# 780-00036_rev1_Sch_Crate_Slot_Power_Inte.net
KiCad netlist of a schematic drawn in Altium Designer
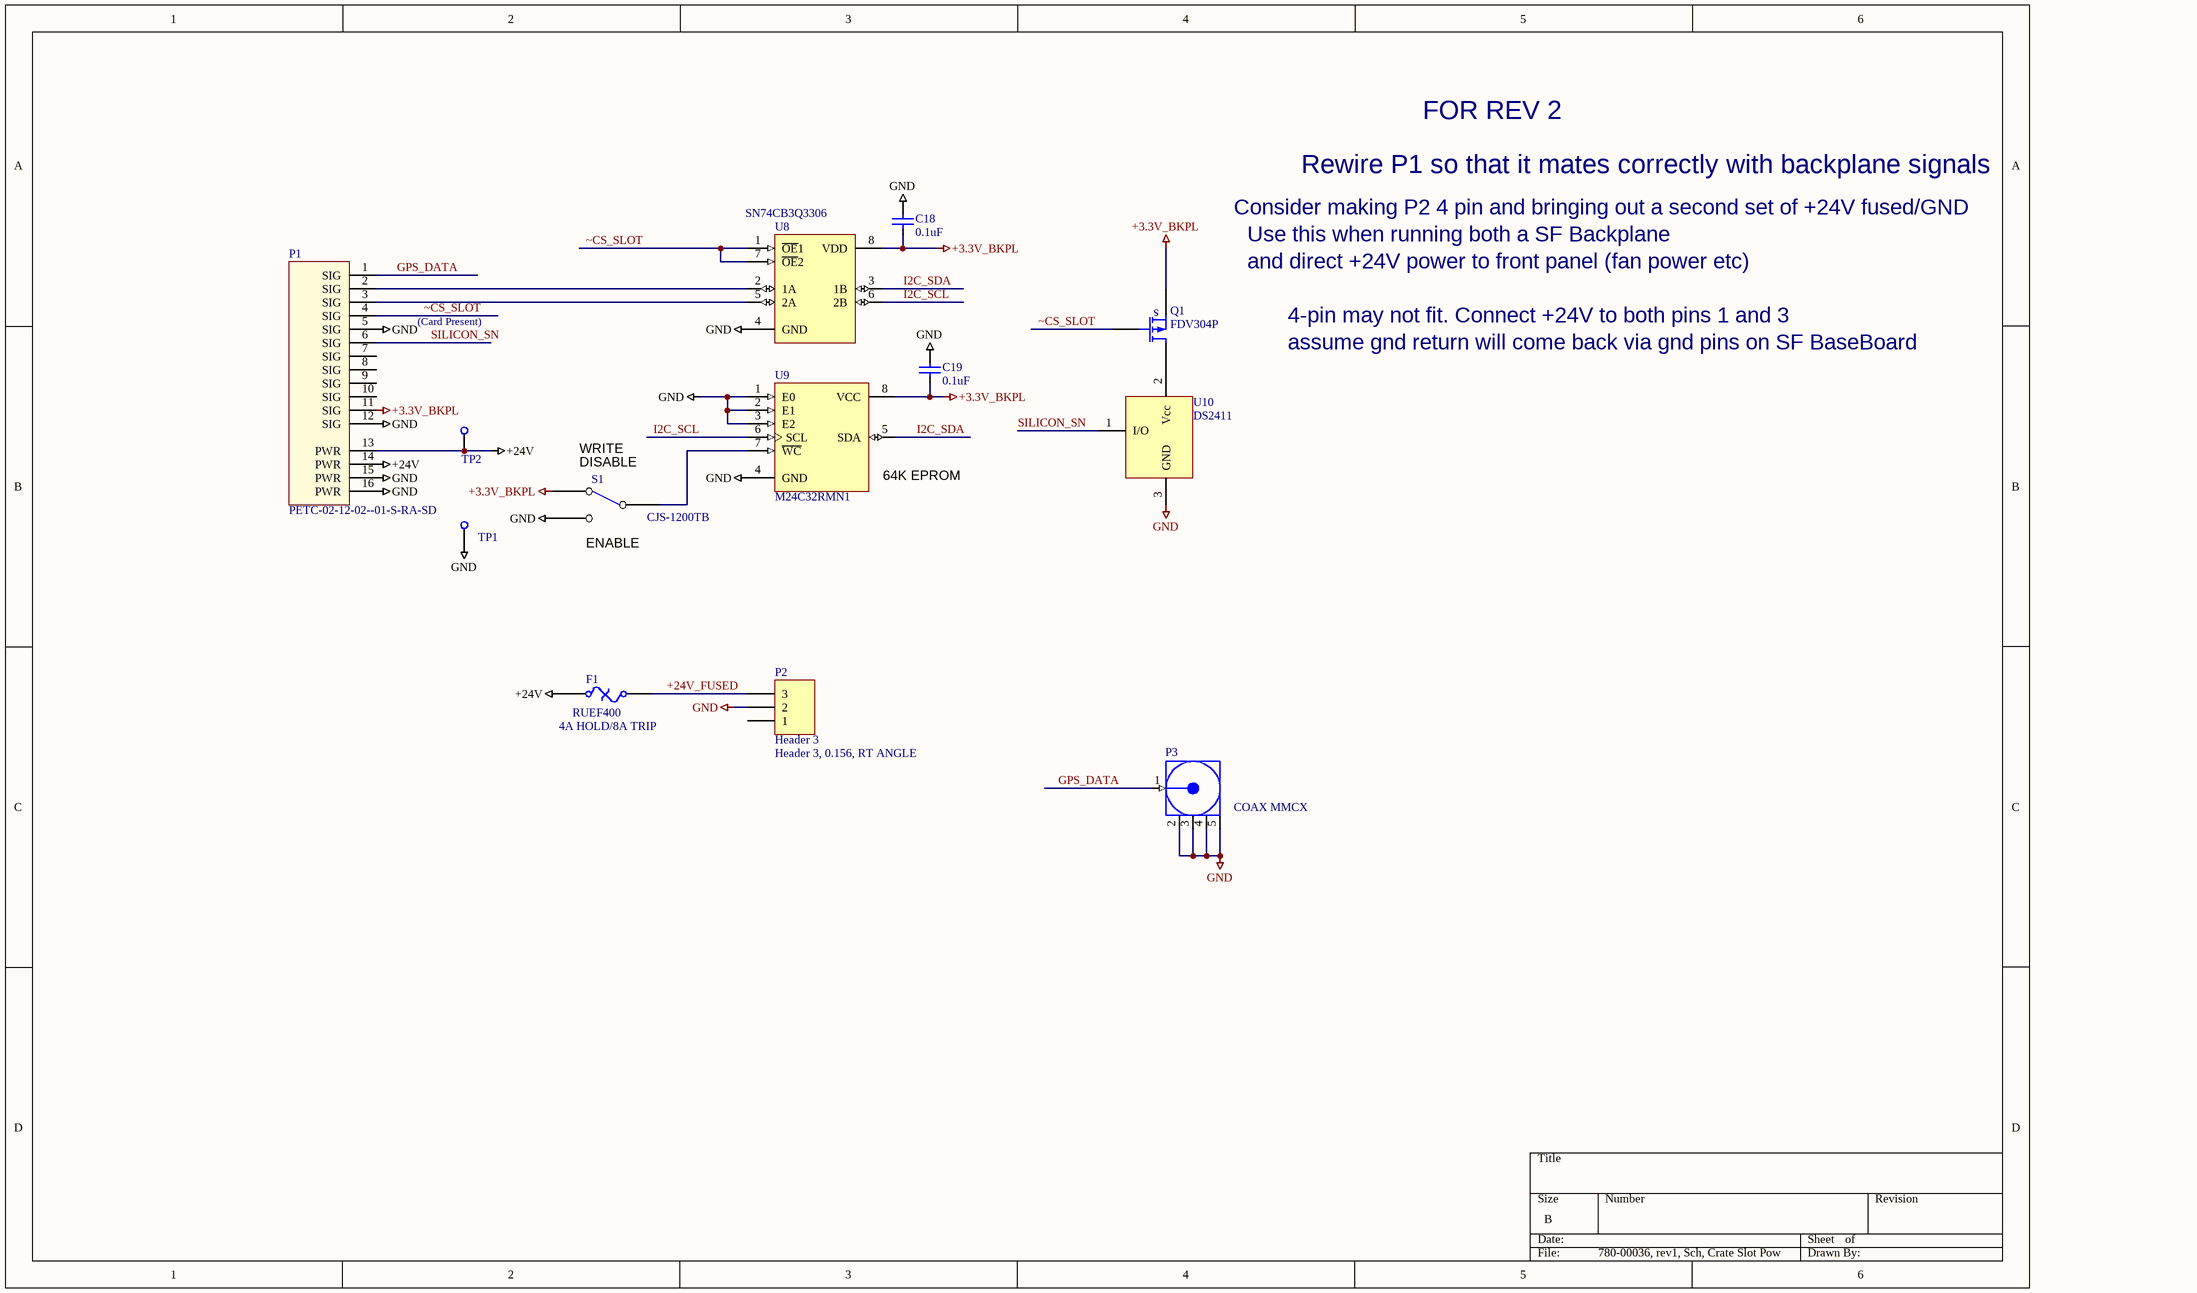
[diagram p0: 780-00036, rev1, Sch, Crate Slot Power Interface.SchDoc]

(export (version "E")
  (design (tool "Eeschema 10.0.6"))
  (components
    (comp (ref "C18")
      (value "0.1uF")
      (footprint "SMD_0805")
      (description "Capacitor")
      (fields (field (name "MANUFACTURER") "AVX") (field (name "Comment") "Cap SMD"))
      (libsource (lib "Richs Schematic Components") (part "Cap SMD"))
    )
    (comp (ref "C19")
      (value "0.1uF")
      (footprint "SMD_0805")
      (description "Capacitor")
      (fields (field (name "MANUFACTURER") "AVX") (field (name "Comment") "Cap SMD"))
      (libsource (lib "Richs Schematic Components") (part "Cap SMD"))
    )
    (comp (ref "F1")
      (value "RUEF400")
      (footprint "PolySwitch Radial 0.2")
      (description "PolySwitch RUE Series")
      (fields
        (field (name "MANUFACTURER") "Tyco Electronics")
        (field (name "ALTIUM_VALUE") "4A HOLD/8A TRIP")
      )
      (libsource (lib "Richs Schematic Components") (part "Fuse Thermal"))
    )
    (comp (ref "P1")
      (value "PETC-02-12-02--01-S-RA-SD")
      (footprint "PETC-02-12-02-01-RA")
      (description "SAMTEC, SIGNAL(12)+PWR(4)")
      (fields (field (name "MANUFACTURER") "SAMTEC"))
      (libsource (lib "Richs Schematic Components") (part "PETC-02-12-02--01-S-RA-SD"))
    )
    (comp (ref "P2")
      (value "Header 3")
      (footprint "HDR 1X3 0.156\" - RT ANGLE")
      (description "Header, 3-Pin, 0.156, RT ANGLE")
      (fields
        (field (name "MANUFACTURER") "TE Connectivity")
        (field (name "ALTIUM_VALUE") "Header 3, 0.156, RT ANGLE")
      )
      (libsource (lib "Richs Schematic Components") (part "Header 3, 0.156 RT ANGLE"))
    )
    (comp (ref "P3")
      (value "COAX MMCX")
      (footprint "Miscellaneous Connectors:MMCX2.54-V5")
      (description "RF Coaxial PCB Connector, MMCX; Thru-Hole, Vertical Mount Plug,  50 Ohm Impedance")
      (fields (field (name "MANUFACTURER") "Emerson"))
      (libsource (lib "Richs Schematic Components") (part "COAX-M"))
    )
    (comp (ref "Q1")
      (value "FDV304P")
      (footprint "SMD_SOT23_3")
      (description "P-MOSFET LOGIC LEVEL")
      (fields (field (name "MANUFACTURER") "Fairchild"))
      (libsource (lib "Richs Schematic Components") (part "FDV304P"))
    )
    (comp (ref "S1")
      (value "CJS-1200TB")
      (footprint "CAS-120B")
      (fields (field (name "MANUFACTURER") "Copal Electronics"))
      (libsource (lib "JON_1_Library") (part "SW_SPDT_DOUG"))
    )
    (comp (ref "TP1")
      (value "Test Point SMD")
      (footprint "SMD_TEST POINT")
      (description "SMD loop test point")
      (libsource (lib "Richs Schematic Components") (part "Test Point SMD"))
    )
    (comp (ref "TP2")
      (value "Test Point SMD")
      (footprint "SMD_TEST POINT")
      (description "SMD loop test point")
      (libsource (lib "Richs Schematic Components") (part "Test Point SMD"))
    )
    (comp (ref "U8")
      (value "SN74CB3Q3306")
      (footprint "PW008_N")
      (description "Dual FET Bus Switch")
      (fields (field (name "MANUFACTURER") "TI") (field (name "Comment") "SN74CBT3306PWLE"))
      (libsource (lib "TI Logic Switch") (part "SN74CBT3306PWLE"))
    )
    (comp (ref "U9")
      (value "M24C32RMN1")
      (footprint "SOP8_N")
      (description "32 Kbit Serial I²C Bus EEPROM")
      (libsource (lib "ST Memory EEPROM Serial") (part "M24C32RMN1"))
    )
    (comp (ref "U10")
      (value "DS2411")
      (footprint "SMD_SOT23_3")
      (description "Silicon Serial Number")
      (fields (field (name "MANUFACTURER") "MAXIM"))
      (libsource (lib "Richs Schematic Components") (part "DS2411"))
    )
  )
  (nets
    (net (code "1") (name "+3.3V_BKPL") (class "Default")
      (node (ref "C18") (pin "1") (pinfunction "1_1") (pintype "passive"))
      (node (ref "C19") (pin "1") (pinfunction "1_1") (pintype "passive"))
      (node (ref "P1") (pin "11") (pinfunction "SIG_11") (pintype "passive"))
      (node (ref "Q1") (pin "2") (pinfunction "S_2") (pintype "passive"))
      (node (ref "S1") (pin "3") (pinfunction "NC_3") (pintype "passive"))
      (node (ref "U8") (pin "8") (pinfunction "VDD_8") (pintype "power_in"))
      (node (ref "U9") (pin "8") (pinfunction "VCC_8") (pintype "power_in"))
    )
    (net (code "2") (name "+24V") (class "Default")
      (node (ref "F1") (pin "1") (pinfunction "1_1") (pintype "passive"))
      (node (ref "P1") (pin "13") (pinfunction "PWR_13") (pintype "passive"))
      (node (ref "P1") (pin "14") (pinfunction "PWR_14") (pintype "passive"))
      (node (ref "TP2") (pin "1") (pinfunction "TP_1") (pintype "passive"))
    )
    (net (code "3") (name "/+24V_FUSED") (class "Default")
      (node (ref "F1") (pin "2") (pinfunction "2_2") (pintype "passive"))
      (node (ref "P2") (pin "3") (pinfunction "3_3") (pintype "passive"))
    )
    (net (code "4") (name "/GPS_DATA") (class "Default")
      (node (ref "P1") (pin "1") (pinfunction "SIG_1") (pintype "passive"))
      (node (ref "P3") (pin "1") (pinfunction "Signal_1") (pintype "input"))
    )
    (net (code "5") (name "/I2C_SCL") (class "Default")
      (node (ref "U8") (pin "6") (pinfunction "2B_6") (pintype "bidirectional"))
      (node (ref "U9") (pin "6") (pinfunction "SCL_6") (pintype "input"))
    )
    (net (code "6") (name "/I2C_SDA") (class "Default")
      (node (ref "U8") (pin "3") (pinfunction "1B_3") (pintype "bidirectional"))
      (node (ref "U9") (pin "5") (pinfunction "SDA_5") (pintype "bidirectional"))
    )
    (net (code "7") (name "/SILICON_SN") (class "Default")
      (node (ref "P1") (pin "6") (pinfunction "SIG_6") (pintype "passive"))
      (node (ref "U10") (pin "1") (pinfunction "I/O_1") (pintype "passive"))
    )
    (net (code "8") (name "/~CS_SLOT") (class "Default")
      (node (ref "P1") (pin "4") (pinfunction "SIG_4") (pintype "passive"))
      (node (ref "Q1") (pin "1") (pinfunction "G_1") (pintype "passive"))
      (node (ref "U8") (pin "1") (pinfunction "~{OE}1_1") (pintype "input"))
      (node (ref "U8") (pin "7") (pinfunction "~{OE}2_7") (pintype "input"))
    )
    (net (code "9") (name "GND") (class "Default")
      (node (ref "C18") (pin "2") (pinfunction "2_2") (pintype "passive"))
      (node (ref "C19") (pin "2") (pinfunction "2_2") (pintype "passive"))
      (node (ref "P1") (pin "12") (pinfunction "SIG_12") (pintype "passive"))
      (node (ref "P1") (pin "15") (pinfunction "PWR_15") (pintype "passive"))
      (node (ref "P1") (pin "16") (pinfunction "PWR_16") (pintype "passive"))
      (node (ref "P1") (pin "5") (pinfunction "SIG_5") (pintype "passive"))
      (node (ref "P2") (pin "2") (pinfunction "2_2") (pintype "passive"))
      (node (ref "P3") (pin "2") (pinfunction "GND_2") (pintype "power_in"))
      (node (ref "P3") (pin "3") (pinfunction "GND_3") (pintype "power_in"))
      (node (ref "P3") (pin "4") (pinfunction "GND_4") (pintype "power_in"))
      (node (ref "P3") (pin "5") (pinfunction "GND_5") (pintype "power_in"))
      (node (ref "S1") (pin "1") (pinfunction "NO_1") (pintype "passive"))
      (node (ref "TP1") (pin "1") (pinfunction "TP_1") (pintype "passive"))
      (node (ref "U10") (pin "3") (pinfunction "GND_3") (pintype "passive"))
      (node (ref "U8") (pin "4") (pinfunction "GND_4") (pintype "power_in"))
      (node (ref "U9") (pin "1") (pinfunction "E0_1") (pintype "input"))
      (node (ref "U9") (pin "2") (pinfunction "E1_2") (pintype "input"))
      (node (ref "U9") (pin "3") (pinfunction "E2_3") (pintype "input"))
      (node (ref "U9") (pin "4") (pinfunction "GND_4") (pintype "power_in"))
    )
    (net (code "10") (name "Net-(Q1-D)") (class "Default")
      (node (ref "Q1") (pin "3") (pinfunction "D_3") (pintype "passive"))
      (node (ref "U10") (pin "2") (pinfunction "Vcc_2") (pintype "passive"))
    )
    (net (code "11") (name "Net-(S1-COM)") (class "Default")
      (node (ref "S1") (pin "2") (pinfunction "COM_2") (pintype "passive"))
      (node (ref "U9") (pin "7") (pinfunction "~{WC}_7") (pintype "input"))
    )
    (net (code "12") (name "Net-(U8-1A)") (class "Default")
      (node (ref "P1") (pin "2") (pinfunction "SIG_2") (pintype "passive"))
      (node (ref "U8") (pin "2") (pinfunction "1A_2") (pintype "bidirectional"))
    )
    (net (code "13") (name "Net-(U8-2A)") (class "Default")
      (node (ref "P1") (pin "3") (pinfunction "SIG_3") (pintype "passive"))
      (node (ref "U8") (pin "5") (pinfunction "2A_5") (pintype "bidirectional"))
    )
    (net (code "14") (name "unconnected-(P1-SIG-Pad7)") (class "Default")
      (node (ref "P1") (pin "7") (pinfunction "SIG_7") (pintype "passive"))
    )
    (net (code "15") (name "unconnected-(P1-SIG-Pad8)") (class "Default")
      (node (ref "P1") (pin "8") (pinfunction "SIG_8") (pintype "passive"))
    )
    (net (code "16") (name "unconnected-(P1-SIG-Pad9)") (class "Default")
      (node (ref "P1") (pin "9") (pinfunction "SIG_9") (pintype "passive"))
    )
    (net (code "17") (name "unconnected-(P1-SIG-Pad10)") (class "Default")
      (node (ref "P1") (pin "10") (pinfunction "SIG_10") (pintype "passive"))
    )
    (net (code "18") (name "unconnected-(P2-Pad1)") (class "Default")
      (node (ref "P2") (pin "1") (pinfunction "1_1") (pintype "passive"))
    )
  )
)
